# longranger_led-001.net
KiCad netlist of a schematic drawn in EAGLE
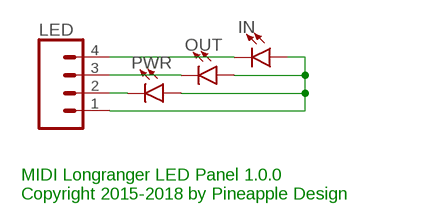
[diagram p0: schematic, sheet 1]

(export (version "E")
  (design (tool "Eeschema 10.0.6"))
  (components
    (comp (ref "IN")
      (value "LED3MM")
      (footprint "eagle-import:LED_3MM")
      (libsource (lib "eagle-import") (part "LED3MM"))
    )
    (comp (ref "LED")
      (value "CONN_04JST-PTH-VERT")
      (footprint "eagle-import:JST-4-PTH-VERT")
      (libsource (lib "eagle-import") (part "CONN_04JST-PTH-VERT"))
    )
    (comp (ref "OUT")
      (value "LED3MM")
      (footprint "eagle-import:LED_3MM")
      (libsource (lib "eagle-import") (part "LED3MM"))
    )
    (comp (ref "PWR")
      (value "LED3MM")
      (footprint "eagle-import:LED_3MM")
      (libsource (lib "eagle-import") (part "LED3MM"))
    )
  )
  (nets
    (net (code "1") (name "Net-(IN-C)") (class "Default")
      (node (ref "IN") (pin "K") (pinfunction "C_K") (pintype "passive"))
      (node (ref "LED") (pin "4") (pinfunction "4_4") (pintype "passive"))
    )
    (net (code "2") (name "Net-(IN-PadA)") (class "Default")
      (node (ref "IN") (pin "A") (pinfunction "A_A") (pintype "passive"))
      (node (ref "LED") (pin "1") (pinfunction "1_1") (pintype "passive"))
      (node (ref "OUT") (pin "A") (pinfunction "A_A") (pintype "passive"))
      (node (ref "PWR") (pin "A") (pinfunction "A_A") (pintype "passive"))
    )
    (net (code "3") (name "Net-(OUT-C)") (class "Default")
      (node (ref "LED") (pin "3") (pinfunction "3_3") (pintype "passive"))
      (node (ref "OUT") (pin "K") (pinfunction "C_K") (pintype "passive"))
    )
    (net (code "4") (name "Net-(PWR-C)") (class "Default")
      (node (ref "LED") (pin "2") (pinfunction "2_2") (pintype "passive"))
      (node (ref "PWR") (pin "K") (pinfunction "C_K") (pintype "passive"))
    )
  )
)
